# SI5324_CDR_WR_clocks.net
KiCad netlist of a schematic drawn in Altium Designer
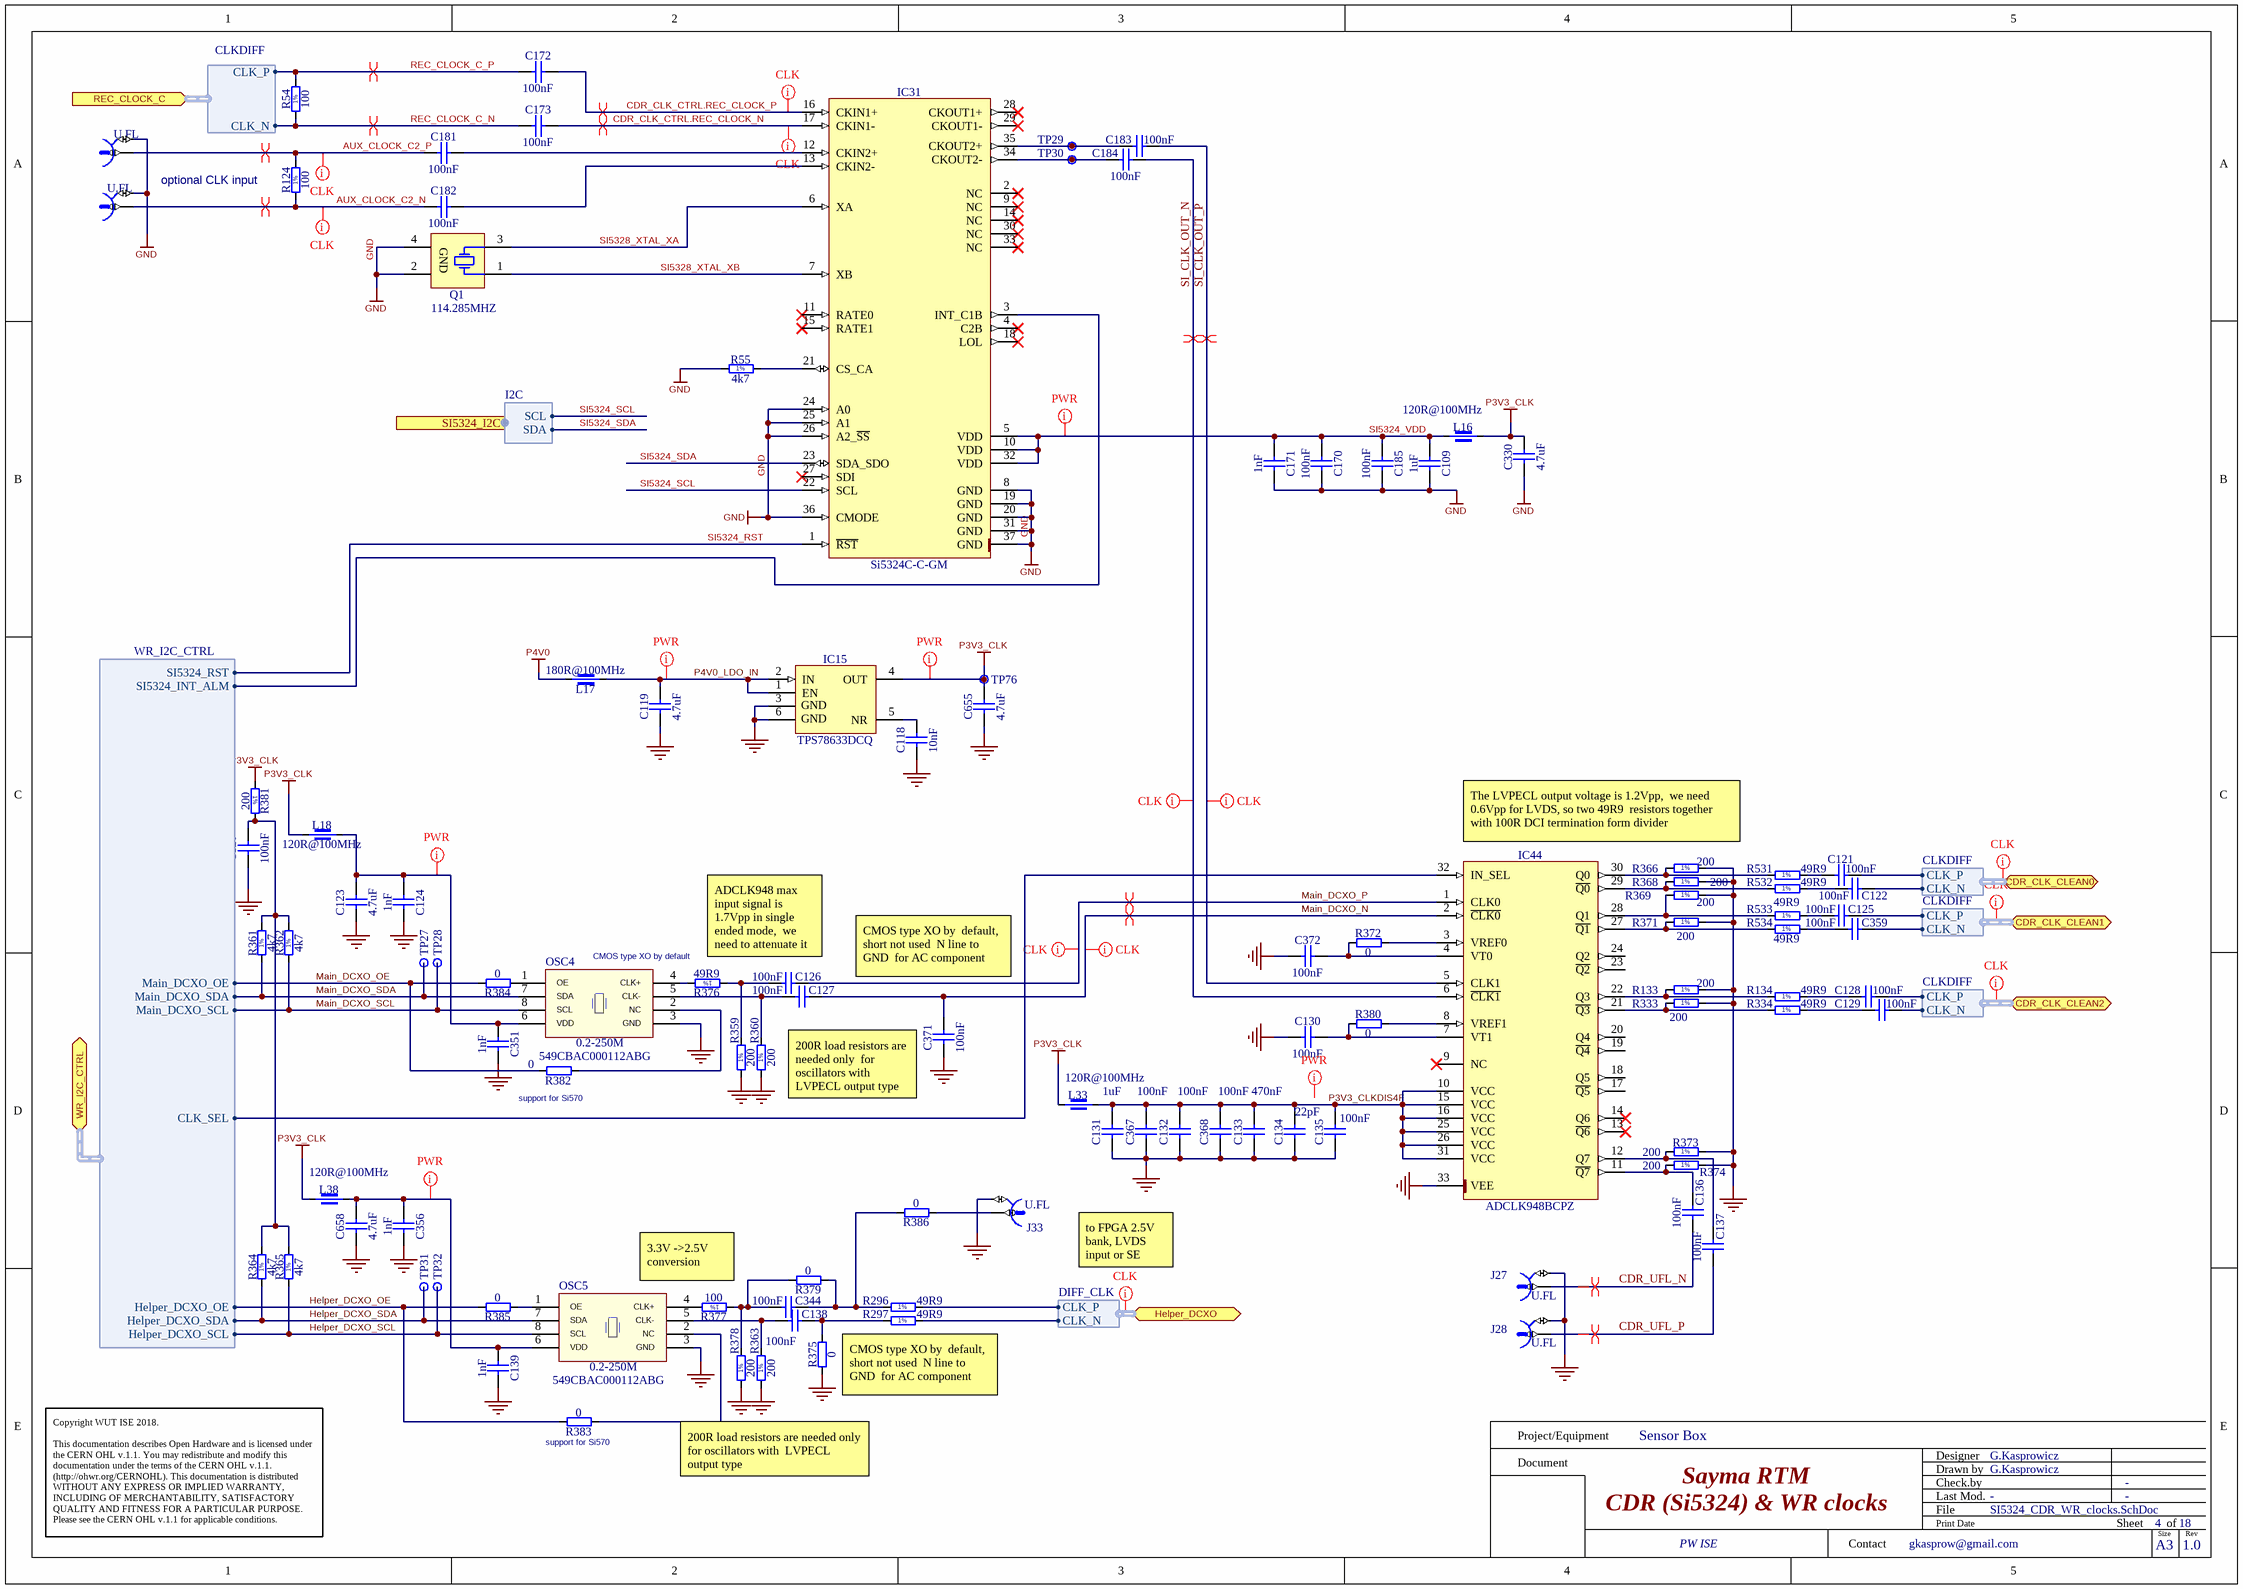
[diagram p0: SI5324_CDR_WR_clocks.SchDoc]

(export (version "E")
  (design (tool "Eeschema 10.0.6"))
  (components
    (comp (ref "C109")
      (value "1uF")
      (footprint "CAPC1005X55N")
      (description "Non-polarised capacitor")
      (fields
        (field (name "MANUFACTURER PART NUMBER") "CC0402_1UF_16V_10%_X5R")
        (field (name "MANUFACTURER") "GENERIC")
        (field (name "AUTHOR") "CERN DEM JLC")
      )
      (libsource (lib "Capacitors") (part "Capacitor - non polarized"))
    )
    (comp (ref "C118")
      (value "10nF")
      (footprint "CAPC1608X87N")
      (description "Non-polarised capacitor")
      (fields
        (field (name "PART NUMBER") "CC0603_10NF_50V_5%_C0G")
        (field (name "VOLTAGE") "50V")
        (field (name "AUTHOR") "CERN DEM JLC")
      )
      (libsource (lib "Capacitors") (part "Capacitor - non polarized"))
    )
    (comp (ref "C119")
      (value "4.7uF")
      (footprint "CAPC1608X90N")
      (description "Non-polarised capacitor")
      (fields
        (field (name "MANUFACTURER PART NUMBER") "CC0603_4.7UF_25V_10%_X5R")
        (field (name "MANUFACTURER") "GENERIC")
        (field (name "AUTHOR") "CERN DEM JLC")
      )
      (libsource (lib "Capacitors") (part "Capacitor - non polarized"))
    )
    (comp (ref "C120")
      (value "100nF")
      (footprint "CAPC0603X33N")
      (description "Non-polarised capacitor")
      (fields
        (field (name "MANUFACTURER PART NUMBER") "CC0201_100NF_6.3V_10%_X5R")
        (field (name "MANUFACTURER") "GENERIC")
        (field (name "AUTHOR") "CERN DEM JLC")
      )
      (libsource (lib "Capacitors") (part "Capacitor - non polarized"))
    )
    (comp (ref "C121")
      (value "100nF")
      (footprint "CAPC0603X33N")
      (description "Non-polarised capacitor")
      (fields
        (field (name "MANUFACTURER PART NUMBER") "CC0201_100NF_6.3V_10%_X5R")
        (field (name "MANUFACTURER") "GENERIC")
        (field (name "AUTHOR") "CERN DEM JLC")
      )
      (libsource (lib "Capacitors") (part "Capacitor - non polarized"))
    )
    (comp (ref "C122")
      (value "100nF")
      (footprint "CAPC0603X33N")
      (description "Non-polarised capacitor")
      (fields
        (field (name "MANUFACTURER PART NUMBER") "CC0201_100NF_6.3V_10%_X5R")
        (field (name "MANUFACTURER") "GENERIC")
        (field (name "AUTHOR") "CERN DEM JLC")
      )
      (libsource (lib "Capacitors") (part "Capacitor - non polarized"))
    )
    (comp (ref "C123")
      (value "4.7uF")
      (footprint "CAPC1608X90N")
      (description "Non-polarised capacitor")
      (fields
        (field (name "MANUFACTURER PART NUMBER") "CC0603_4.7UF_25V_10%_X5R")
        (field (name "MANUFACTURER") "GENERIC")
        (field (name "AUTHOR") "CERN DEM JLC")
      )
      (libsource (lib "Capacitors") (part "Capacitor - non polarized"))
    )
    (comp (ref "C124")
      (value "1nF")
      (footprint "CAPC0603X33N")
      (description "Non-polarised capacitor")
      (fields
        (field (name "MANUFACTURER PART NUMBER") "CC0201_1NF_16V_10%_X5R")
        (field (name "MANUFACTURER") "GENERIC")
        (field (name "AUTHOR") "CERN DEM JLC")
      )
      (libsource (lib "Capacitors") (part "Capacitor - non polarized"))
    )
    (comp (ref "C125")
      (value "100nF")
      (footprint "CAPC0603X33N")
      (description "Non-polarised capacitor")
      (fields
        (field (name "MANUFACTURER PART NUMBER") "CC0201_100NF_6.3V_10%_X5R")
        (field (name "MANUFACTURER") "GENERIC")
        (field (name "AUTHOR") "CERN DEM JLC")
      )
      (libsource (lib "Capacitors") (part "Capacitor - non polarized"))
    )
    (comp (ref "C126")
      (value "100nF")
      (footprint "CAPC1005X55N")
      (description "Non-polarised capacitor")
      (fields
        (field (name "MANUFACTURER PART NUMBER") "CC0402_100NF_16V_10%_X5R")
        (field (name "MANUFACTURER") "GENERIC")
        (field (name "AUTHOR") "CERN DEM JLC")
      )
      (libsource (lib "Capacitors") (part "Capacitor - non polarized"))
    )
    (comp (ref "C127")
      (value "100nF")
      (footprint "CAPC1005X55N")
      (description "Non-polarised capacitor")
      (fields
        (field (name "MANUFACTURER PART NUMBER") "CC0402_100NF_16V_10%_X5R")
        (field (name "MANUFACTURER") "GENERIC")
        (field (name "AUTHOR") "CERN DEM JLC")
      )
      (libsource (lib "Capacitors") (part "Capacitor - non polarized"))
    )
    (comp (ref "C128")
      (value "100nF")
      (footprint "CAPC0603X33N")
      (description "Non-polarised capacitor")
      (fields
        (field (name "MANUFACTURER PART NUMBER") "CC0201_100NF_6.3V_10%_X5R")
        (field (name "MANUFACTURER") "GENERIC")
        (field (name "AUTHOR") "CERN DEM JLC")
      )
      (libsource (lib "Capacitors") (part "Capacitor - non polarized"))
    )
    (comp (ref "C129")
      (value "100nF")
      (footprint "CAPC0603X33N")
      (description "Non-polarised capacitor")
      (fields
        (field (name "MANUFACTURER PART NUMBER") "CC0201_100NF_6.3V_10%_X5R")
        (field (name "MANUFACTURER") "GENERIC")
        (field (name "AUTHOR") "CERN DEM JLC")
      )
      (libsource (lib "Capacitors") (part "Capacitor - non polarized"))
    )
    (comp (ref "C130")
      (value "100nF")
      (footprint "CAPC0603X33N")
      (description "Non-polarised capacitor")
      (fields
        (field (name "MANUFACTURER PART NUMBER") "CC0201_100NF_6.3V_10%_X5R")
        (field (name "MANUFACTURER") "GENERIC")
        (field (name "AUTHOR") "CERN DEM JLC")
      )
      (libsource (lib "Capacitors") (part "Capacitor - non polarized"))
    )
    (comp (ref "C131")
      (value "1uF")
      (footprint "CAPC1005X55N")
      (description "Non-polarised capacitor")
      (fields
        (field (name "MANUFACTURER PART NUMBER") "CC0402_1UF_16V_10%_X5R")
        (field (name "MANUFACTURER") "GENERIC")
        (field (name "AUTHOR") "CERN DEM JLC")
      )
      (libsource (lib "Capacitors") (part "Capacitor - non polarized"))
    )
    (comp (ref "C132")
      (value "100nF")
      (footprint "CAPC0603X33N")
      (description "Non-polarised capacitor")
      (fields
        (field (name "MANUFACTURER PART NUMBER") "CC0201_100NF_6.3V_10%_X5R")
        (field (name "MANUFACTURER") "GENERIC")
        (field (name "AUTHOR") "CERN DEM JLC")
      )
      (libsource (lib "Capacitors") (part "Capacitor - non polarized"))
    )
    (comp (ref "C133")
      (value "470nF")
      (footprint "CAPC1005X55N")
      (description "Non-polarised capacitor")
      (fields
        (field (name "MANUFACTURER PART NUMBER") "CC0402_470NF_16V_10%_X5R")
        (field (name "MANUFACTURER") "GENERIC")
        (field (name "AUTHOR") "CERN DEM JLC")
      )
      (libsource (lib "Capacitors") (part "Capacitor - non polarized"))
    )
    (comp (ref "C134")
      (value "22pF")
      (footprint "CAPC1005X55N")
      (description "Non-polarised capacitor")
      (fields
        (field (name "MANUFACTURER PART NUMBER") "CC0402_22PF_50V_5%_C0G")
        (field (name "MANUFACTURER") "GENERIC")
        (field (name "AUTHOR") "CERN DEM JLC")
      )
      (libsource (lib "Capacitors") (part "Capacitor - non polarized"))
    )
    (comp (ref "C135")
      (value "100nF")
      (footprint "CAPC0603X33N")
      (description "Non-polarised capacitor")
      (fields
        (field (name "MANUFACTURER PART NUMBER") "CC0201_100NF_6.3V_10%_X5R")
        (field (name "MANUFACTURER") "GENERIC")
        (field (name "AUTHOR") "CERN DEM JLC")
      )
      (libsource (lib "Capacitors") (part "Capacitor - non polarized"))
    )
    (comp (ref "C136")
      (value "100nF")
      (footprint "CAPC0603X33N")
      (description "Non-polarised capacitor")
      (fields
        (field (name "MANUFACTURER PART NUMBER") "CC0201_100NF_6.3V_10%_X5R")
        (field (name "MANUFACTURER") "GENERIC")
        (field (name "AUTHOR") "CERN DEM JLC")
      )
      (libsource (lib "Capacitors") (part "Capacitor - non polarized"))
    )
    (comp (ref "C137")
      (value "100nF")
      (footprint "CAPC0603X33N")
      (description "Non-polarised capacitor")
      (fields
        (field (name "MANUFACTURER PART NUMBER") "CC0201_100NF_6.3V_10%_X5R")
        (field (name "MANUFACTURER") "GENERIC")
        (field (name "AUTHOR") "CERN DEM JLC")
      )
      (libsource (lib "Capacitors") (part "Capacitor - non polarized"))
    )
    (comp (ref "C138")
      (value "100nF")
      (footprint "CAPC1005X55N")
      (description "Non-polarised capacitor")
      (fields
        (field (name "MANUFACTURER PART NUMBER") "CC0402_100NF_16V_10%_X5R")
        (field (name "MANUFACTURER") "GENERIC")
        (field (name "AUTHOR") "CERN DEM JLC")
      )
      (libsource (lib "Capacitors") (part "Capacitor - non polarized"))
    )
    (comp (ref "C139")
      (value "1nF")
      (footprint "CAPC0603X33N")
      (description "Non-polarised capacitor")
      (fields
        (field (name "MANUFACTURER PART NUMBER") "CC0201_1NF_16V_10%_X5R")
        (field (name "MANUFACTURER") "GENERIC")
        (field (name "AUTHOR") "CERN DEM JLC")
      )
      (libsource (lib "Capacitors") (part "Capacitor - non polarized"))
    )
    (comp (ref "C170")
      (value "100nF")
      (footprint "CAPC0603X33N")
      (description "Non-polarised capacitor")
      (fields
        (field (name "MANUFACTURER PART NUMBER") "CC0201_100NF_6.3V_10%_X5R")
        (field (name "MANUFACTURER") "GENERIC")
        (field (name "AUTHOR") "CERN DEM JLC")
      )
      (libsource (lib "Capacitors") (part "Capacitor - non polarized"))
    )
    (comp (ref "C171")
      (value "1nF")
      (footprint "CAPC0603X33N")
      (description "Non-polarised capacitor")
      (fields
        (field (name "MANUFACTURER PART NUMBER") "CC0201_1NF_16V_10%_X5R")
        (field (name "MANUFACTURER") "GENERIC")
        (field (name "AUTHOR") "CERN DEM JLC")
      )
      (libsource (lib "Capacitors") (part "Capacitor - non polarized"))
    )
    (comp (ref "C172")
      (value "100nF")
      (footprint "CAPC0603X33N")
      (description "Non-polarised capacitor")
      (fields
        (field (name "MANUFACTURER PART NUMBER") "CC0201_100NF_6.3V_10%_X5R")
        (field (name "MANUFACTURER") "GENERIC")
        (field (name "AUTHOR") "CERN DEM JLC")
      )
      (libsource (lib "Capacitors") (part "Capacitor - non polarized"))
    )
    (comp (ref "C173")
      (value "100nF")
      (footprint "CAPC0603X33N")
      (description "Non-polarised capacitor")
      (fields
        (field (name "MANUFACTURER PART NUMBER") "CC0201_100NF_6.3V_10%_X5R")
        (field (name "MANUFACTURER") "GENERIC")
        (field (name "AUTHOR") "CERN DEM JLC")
      )
      (libsource (lib "Capacitors") (part "Capacitor - non polarized"))
    )
    (comp (ref "C181")
      (value "100nF")
      (footprint "CAPC0603X33N")
      (description "Non-polarised capacitor")
      (fields
        (field (name "MANUFACTURER PART NUMBER") "CC0201_100NF_6.3V_10%_X5R")
        (field (name "MANUFACTURER") "GENERIC")
        (field (name "AUTHOR") "CERN DEM JLC")
      )
      (libsource (lib "Capacitors") (part "Capacitor - non polarized"))
    )
    (comp (ref "C182")
      (value "100nF")
      (footprint "CAPC0603X33N")
      (description "Non-polarised capacitor")
      (fields
        (field (name "MANUFACTURER PART NUMBER") "CC0201_100NF_6.3V_10%_X5R")
        (field (name "MANUFACTURER") "GENERIC")
        (field (name "AUTHOR") "CERN DEM JLC")
      )
      (libsource (lib "Capacitors") (part "Capacitor - non polarized"))
    )
    (comp (ref "C183")
      (value "100nF")
      (footprint "CAPC0603X33N")
      (description "Non-polarised capacitor")
      (fields
        (field (name "MANUFACTURER PART NUMBER") "CC0201_100NF_6.3V_10%_X5R")
        (field (name "MANUFACTURER") "GENERIC")
        (field (name "AUTHOR") "CERN DEM JLC")
      )
      (libsource (lib "Capacitors") (part "Capacitor - non polarized"))
    )
    (comp (ref "C184")
      (value "100nF")
      (footprint "CAPC0603X33N")
      (description "Non-polarised capacitor")
      (fields
        (field (name "MANUFACTURER PART NUMBER") "CC0201_100NF_6.3V_10%_X5R")
        (field (name "MANUFACTURER") "GENERIC")
        (field (name "AUTHOR") "CERN DEM JLC")
      )
      (libsource (lib "Capacitors") (part "Capacitor - non polarized"))
    )
    (comp (ref "C185")
      (value "100nF")
      (footprint "CAPC0603X33N")
      (description "Non-polarised capacitor")
      (fields
        (field (name "MANUFACTURER PART NUMBER") "CC0201_100NF_6.3V_10%_X5R")
        (field (name "MANUFACTURER") "GENERIC")
        (field (name "AUTHOR") "CERN DEM JLC")
      )
      (libsource (lib "Capacitors") (part "Capacitor - non polarized"))
    )
    (comp (ref "C330")
      (value "4.7uF")
      (footprint "CAPC1608X90N")
      (description "Non-polarised capacitor")
      (fields
        (field (name "MANUFACTURER PART NUMBER") "CC0603_4.7UF_25V_10%_X5R")
        (field (name "MANUFACTURER") "GENERIC")
        (field (name "AUTHOR") "CERN DEM JLC")
      )
      (libsource (lib "Capacitors") (part "Capacitor - non polarized"))
    )
    (comp (ref "C344")
      (value "100nF")
      (footprint "CAPC1005X55N")
      (description "Non-polarised capacitor")
      (fields
        (field (name "MANUFACTURER PART NUMBER") "CC0402_100NF_16V_10%_X5R")
        (field (name "MANUFACTURER") "GENERIC")
        (field (name "AUTHOR") "CERN DEM JLC")
      )
      (libsource (lib "Capacitors") (part "Capacitor - non polarized"))
    )
    (comp (ref "C351")
      (value "1nF")
      (footprint "CAPC0603X33N")
      (description "Non-polarised capacitor")
      (fields
        (field (name "MANUFACTURER PART NUMBER") "CC0201_1NF_16V_10%_X5R")
        (field (name "MANUFACTURER") "GENERIC")
        (field (name "AUTHOR") "CERN DEM JLC")
      )
      (libsource (lib "Capacitors") (part "Capacitor - non polarized"))
    )
    (comp (ref "C356")
      (value "1nF")
      (footprint "CAPC0603X33N")
      (description "Non-polarised capacitor")
      (fields
        (field (name "MANUFACTURER PART NUMBER") "CC0201_1NF_16V_10%_X5R")
        (field (name "MANUFACTURER") "GENERIC")
        (field (name "AUTHOR") "CERN DEM JLC")
      )
      (libsource (lib "Capacitors") (part "Capacitor - non polarized"))
    )
    (comp (ref "C359")
      (value "100nF")
      (footprint "CAPC0603X33N")
      (description "Non-polarised capacitor")
      (fields
        (field (name "MANUFACTURER PART NUMBER") "CC0201_100NF_6.3V_10%_X5R")
        (field (name "MANUFACTURER") "GENERIC")
        (field (name "AUTHOR") "CERN DEM JLC")
      )
      (libsource (lib "Capacitors") (part "Capacitor - non polarized"))
    )
    (comp (ref "C367")
      (value "100nF")
      (footprint "CAPC0603X33N")
      (description "Non-polarised capacitor")
      (fields
        (field (name "MANUFACTURER PART NUMBER") "CC0201_100NF_6.3V_10%_X5R")
        (field (name "MANUFACTURER") "GENERIC")
        (field (name "AUTHOR") "CERN DEM JLC")
      )
      (libsource (lib "Capacitors") (part "Capacitor - non polarized"))
    )
    (comp (ref "C368")
      (value "100nF")
      (footprint "CAPC0603X33N")
      (description "Non-polarised capacitor")
      (fields
        (field (name "MANUFACTURER PART NUMBER") "CC0201_100NF_6.3V_10%_X5R")
        (field (name "MANUFACTURER") "GENERIC")
        (field (name "AUTHOR") "CERN DEM JLC")
      )
      (libsource (lib "Capacitors") (part "Capacitor - non polarized"))
    )
    (comp (ref "C371")
      (value "100nF")
      (footprint "CAPC0603X33N")
      (description "Non-polarised capacitor")
      (fields
        (field (name "MANUFACTURER PART NUMBER") "CC0201_100NF_6.3V_10%_X5R")
        (field (name "MANUFACTURER") "GENERIC")
        (field (name "AUTHOR") "CERN DEM JLC")
      )
      (libsource (lib "Capacitors") (part "Capacitor - non polarized"))
    )
    (comp (ref "C372")
      (value "100nF")
      (footprint "CAPC0603X33N")
      (description "Non-polarised capacitor")
      (fields
        (field (name "MANUFACTURER PART NUMBER") "CC0201_100NF_6.3V_10%_X5R")
        (field (name "MANUFACTURER") "GENERIC")
        (field (name "AUTHOR") "CERN DEM JLC")
      )
      (libsource (lib "Capacitors") (part "Capacitor - non polarized"))
    )
    (comp (ref "C655")
      (value "4.7uF")
      (footprint "CAPC1608X90N")
      (description "Non-polarised capacitor")
      (fields
        (field (name "MANUFACTURER PART NUMBER") "CC0603_4.7UF_25V_10%_X5R")
        (field (name "MANUFACTURER") "GENERIC")
        (field (name "AUTHOR") "CERN DEM JLC")
      )
      (libsource (lib "Capacitors") (part "Capacitor - non polarized"))
    )
    (comp (ref "C658")
      (value "4.7uF")
      (footprint "CAPC1608X90N")
      (description "Non-polarised capacitor")
      (fields
        (field (name "MANUFACTURER PART NUMBER") "CC0603_4.7UF_25V_10%_X5R")
        (field (name "MANUFACTURER") "GENERIC")
        (field (name "AUTHOR") "CERN DEM JLC")
      )
      (libsource (lib "Capacitors") (part "Capacitor - non polarized"))
    )
    (comp (ref "IC15")
      (value "TPS78633DCQ")
      (footprint "SOT127P700X180-6N")
      (description "Ultralow-Noise, High-PSRR, Fast, RF, 1.5A Low-Dropout Linear Regulator")
      (fields (field (name "MANUFACTURER") "TEXAS INSTRUMENTS") (field (name "AUTHOR") "CERN DEM JMW"))
      (libsource (lib "ICs And Semiconductors") (part "TPS786xxDCQ"))
    )
    (comp (ref "IC31")
      (value "Si5324C-C-GM")
      (footprint "QFN50P600X600X90-37N-S425")
      (description "Any Frequency Precision Clock Multiplier/Jitter Attenuator")
      (fields (field (name "MANUFACTURER") "SILICON LABS") (field (name "AUTHOR") "CERN DEM JLC"))
      (libsource (lib "ICs And Semiconductors") (part "Si5324"))
    )
    (comp (ref "IC44")
      (value "ADCLK948BCPZ")
      (footprint "QFN50P500X500X80-33N-S285")
      (description "Two Selectable Inputs, 8 LVPECL Outputs, SiGe Clock Fanout Buffer")
      (fields (field (name "MANUFACTURER") "ANALOG DEVICES") (field (name "AUTHOR") "CERN DEM MR"))
      (libsource (lib "ICs And Semiconductors") (part "ADCLK948"))
    )
    (comp (ref "J5")
      (value "U.FL")
      (footprint "HIROSE_U.FL-R-SMT-1(10)")
      (fields
        (field (name "FAMILY") "U.FL")
        (field (name "MANUFACTURER PART NUMBER") "U.FL-R-SMT-1(10)")
        (field (name "MANUFACTURER") "HIROSE (HRS)")
        (field (name "PART NUMBER") "HIROSE_U.FL-R-SMT-1(10)")
        (field (name "AUTHOR") "CERN DEM JLC")
      )
      (libsource (lib "Connectors") (part "Coax_1Male_1Shield"))
    )
    (comp (ref "J6")
      (value "U.FL")
      (footprint "HIROSE_U.FL-R-SMT-1(10)")
      (fields
        (field (name "FAMILY") "U.FL")
        (field (name "MANUFACTURER PART NUMBER") "U.FL-R-SMT-1(10)")
        (field (name "MANUFACTURER") "HIROSE (HRS)")
        (field (name "PART NUMBER") "HIROSE_U.FL-R-SMT-1(10)")
        (field (name "AUTHOR") "CERN DEM JLC")
      )
      (libsource (lib "Connectors") (part "Coax_1Male_1Shield"))
    )
    (comp (ref "J27")
      (value "U.FL")
      (footprint "HIROSE_U.FL-R-SMT-1(10)")
      (fields
        (field (name "MANUFACTURER PART NUMBER") "U.FL-R-SMT-1(10)")
        (field (name "MANUFACTURER") "HIROSE (HRS)")
        (field (name "PART NUMBER") "HIROSE_U.FL-R-SMT-1(10)")
        (field (name "AUTHOR") "CERN DEM JLC")
      )
      (libsource (lib "Connectors") (part "Coax_1Male_1Shield"))
    )
    (comp (ref "J28")
      (value "U.FL")
      (footprint "HIROSE_U.FL-R-SMT-1(10)")
      (fields
        (field (name "MANUFACTURER PART NUMBER") "U.FL-R-SMT-1(10)")
        (field (name "MANUFACTURER") "HIROSE (HRS)")
        (field (name "PART NUMBER") "HIROSE_U.FL-R-SMT-1(10)")
        (field (name "AUTHOR") "CERN DEM JLC")
      )
      (libsource (lib "Connectors") (part "Coax_1Male_1Shield"))
    )
    (comp (ref "J33")
      (value "U.FL")
      (footprint "HIROSE_U.FL-R-SMT-1(10)")
      (fields
        (field (name "MANUFACTURER PART NUMBER") "U.FL-R-SMT-1(10)")
        (field (name "MANUFACTURER") "HIROSE (HRS)")
        (field (name "PART NUMBER") "HIROSE_U.FL-R-SMT-1(10)")
        (field (name "AUTHOR") "CERN DEM JLC")
      )
      (libsource (lib "") (part "Coax_1Male_1Shield_1"))
    )
    (comp (ref "L16")
      (value "120R@100MHz")
      (footprint "INDC1608X95N")
      (fields
        (field (name "MANUFACTURER PART NUMBER") "BLM18PG121SN1D")
        (field (name "MANUFACTURER") "MURATA")
        (field (name "PART NUMBER") "IND0603_MURATA_BLM18PG121SN1D")
        (field (name "AUTHOR") "CERN DEM BC")
      )
      (libsource (lib "") (part "Ferrite Bead_1"))
    )
    (comp (ref "L17")
      (value "180R@100MHz")
      (footprint "INDC4516X180N")
      (fields
        (field (name "MANUFACTURER PART NUMBER") "BLM41PG181SN1L")
        (field (name "MANUFACTURER") "MURATA")
        (field (name "PART NUMBER") "IND1806_MURATA_BLM41PG181SN1L")
        (field (name "AUTHOR") "CERN DEM JLC")
      )
      (libsource (lib "") (part "Ferrite Bead_2"))
    )
    (comp (ref "L18")
      (value "120R@100MHz")
      (footprint "INDC1608X95N")
      (fields
        (field (name "MANUFACTURER PART NUMBER") "BLM18PG121SN1D")
        (field (name "MANUFACTURER") "MURATA")
        (field (name "PART NUMBER") "IND0603_MURATA_BLM18PG121SN1D")
        (field (name "AUTHOR") "CERN DEM BC")
      )
      (libsource (lib "Inductors & Transformers") (part "Ferrite Bead"))
    )
    (comp (ref "L33")
      (value "120R@100MHz")
      (footprint "INDC1608X95N")
      (fields
        (field (name "MANUFACTURER PART NUMBER") "BLM18PG121SN1D")
        (field (name "MANUFACTURER") "MURATA")
        (field (name "PART NUMBER") "IND0603_MURATA_BLM18PG121SN1D")
        (field (name "AUTHOR") "CERN DEM BC")
      )
      (libsource (lib "Inductors & Transformers") (part "Ferrite Bead"))
    )
    (comp (ref "L38")
      (value "120R@100MHz")
      (footprint "INDC1608X95N")
      (fields
        (field (name "MANUFACTURER PART NUMBER") "BLM18PG121SN1D")
        (field (name "MANUFACTURER") "MURATA")
        (field (name "PART NUMBER") "IND0603_MURATA_BLM18PG121SN1D")
        (field (name "AUTHOR") "CERN DEM BC")
      )
      (libsource (lib "Inductors & Transformers") (part "Ferrite Bead"))
    )
    (comp (ref "OSC4")
      (value "0.2-250M")
      (footprint "OSC_SILICON-LAB_SI549")
      (fields
        (field (name "MANUFACTURER PART NUMBER") "549CBAC000112ABG")
        (field (name "MANUFACTURER") "Silabs")
        (field (name "PART NUMBER") "OSC_0.2_250M_SILICON-LAB_549CBAC000112ABG")
      )
      (libsource (lib "LIBRARY_SCH") (part "OSC_SILICON-LAB_SI549"))
    )
    (comp (ref "OSC5")
      (value "0.2-250M")
      (footprint "OSC_SILICON-LAB_SI549")
      (fields
        (field (name "MANUFACTURER PART NUMBER") "549CBAC000112ABG")
        (field (name "MANUFACTURER") "Silabs")
        (field (name "PART NUMBER") "OSC_0.2_250M_SILICON-LAB_549CBAC000112ABG")
      )
      (libsource (lib "LIBRARY_SCH") (part "OSC_SILICON-LAB_SI549"))
    )
    (comp (ref "Q1")
      (value "114.285MHZ")
      (footprint "XTAL_CONNOR_CS")
      (description "Crystal 4 pins 1=XTAL Control 2=GND3=XTAL 4=GND")
      (fields
        (field (name "MANUFACTURER PART NUMBER") "CS-023-114.285M")
        (field (name "MANUFACTURER") "CONNOR-WINFIELD")
        (field (name "AUTHOR") "CERN DEM JLC")
      )
      (libsource (lib "ICs And Semiconductors") (part "Quartz Crystal 1X 2GND 3X 4GND"))
    )
    (comp (ref "R54")
      (value "100")
      (footprint "RESC1005X40N")
      (description "Resistor - 1%")
      (fields
        (field (name "MANUFACTURER PART NUMBER") "R0402_100R_1%_0.0625W_100PPM")
        (field (name "MANUFACTURER") "GENERIC")
        (field (name "AUTHOR") "CERN DEM JLC")
      )
      (libsource (lib "Resistors") (part "Resistor - 1%"))
    )
    (comp (ref "R55")
      (value "4k7")
      (footprint "RESC1005X40N")
      (description "Resistor - 1%")
      (fields
        (field (name "MANUFACTURER PART NUMBER") "R0402_4K7_1%_0.0625W_100PPM")
        (field (name "MANUFACTURER") "GENERIC")
        (field (name "AUTHOR") "CERN DEM JLC")
      )
      (libsource (lib "Resistors") (part "Resistor - 1%"))
    )
    (comp (ref "R124")
      (value "100")
      (footprint "RESC1005X40N")
      (description "Resistor - 1%")
      (fields
        (field (name "MANUFACTURER PART NUMBER") "R0402_100R_1%_0.0625W_100PPM")
        (field (name "MANUFACTURER") "GENERIC")
        (field (name "AUTHOR") "CERN DEM JLC")
      )
      (libsource (lib "Resistors") (part "Resistor - 1%"))
    )
    (comp (ref "R133")
      (value "200")
      (footprint "RESC1005X40N")
      (description "Resistor - 1%")
      (fields
        (field (name "MANUFACTURER PART NUMBER") "R0402_200R_1%_0.0625W_100PPM")
        (field (name "MANUFACTURER") "GENERIC")
        (field (name "AUTHOR") "CERN DEM JLC")
      )
      (libsource (lib "Resistors") (part "Resistor - 1%"))
    )
    (comp (ref "R134")
      (value "49R9")
      (footprint "RESC1005X40N")
      (description "Resistor - 1%")
      (fields
        (field (name "MANUFACTURER PART NUMBER") "R0402_49R9_1%_0.0625W_100PPM")
        (field (name "MANUFACTURER") "GENERIC")
        (field (name "AUTHOR") "CERN DEM JLC")
      )
      (libsource (lib "Resistors") (part "Resistor - 1%"))
    )
    (comp (ref "R296")
      (value "49R9")
      (footprint "RESC1005X40N")
      (description "Resistor - 1%")
      (fields
        (field (name "MANUFACTURER PART NUMBER") "R0402_49R9_1%_0.0625W_100PPM")
        (field (name "MANUFACTURER") "GENERIC")
        (field (name "AUTHOR") "CERN DEM JLC")
      )
      (libsource (lib "Resistors") (part "Resistor - 1%"))
    )
    (comp (ref "R297")
      (value "49R9")
      (footprint "RESC1005X40N")
      (description "Resistor - 1%")
      (fields
        (field (name "MANUFACTURER PART NUMBER") "R0402_49R9_1%_0.0625W_100PPM")
        (field (name "MANUFACTURER") "GENERIC")
        (field (name "AUTHOR") "CERN DEM JLC")
      )
      (libsource (lib "Resistors") (part "Resistor - 1%"))
    )
    (comp (ref "R333")
      (value "200")
      (footprint "RESC1005X40N")
      (description "Resistor - 1%")
      (fields
        (field (name "MANUFACTURER PART NUMBER") "R0402_200R_1%_0.0625W_100PPM")
        (field (name "MANUFACTURER") "GENERIC")
        (field (name "AUTHOR") "CERN DEM JLC")
      )
      (libsource (lib "Resistors") (part "Resistor - 1%"))
    )
    (comp (ref "R334")
      (value "49R9")
      (footprint "RESC1005X40N")
      (description "Resistor - 1%")
      (fields
        (field (name "MANUFACTURER PART NUMBER") "R0402_49R9_1%_0.0625W_100PPM")
        (field (name "MANUFACTURER") "GENERIC")
        (field (name "AUTHOR") "CERN DEM JLC")
      )
      (libsource (lib "Resistors") (part "Resistor - 1%"))
    )
    (comp (ref "R359")
      (value "200")
      (footprint "RESC1005X40N")
      (description "Resistor - 1%")
      (fields
        (field (name "MANUFACTURER PART NUMBER") "R0402_200R_1%_0.0625W_100PPM")
        (field (name "MANUFACTURER") "GENERIC")
        (field (name "AUTHOR") "CERN DEM JLC")
      )
      (libsource (lib "Resistors") (part "Resistor - 1%"))
    )
    (comp (ref "R360")
      (value "200")
      (footprint "RESC1005X40N")
      (description "Resistor - 1%")
      (fields
        (field (name "MANUFACTURER PART NUMBER") "R0402_200R_1%_0.0625W_100PPM")
        (field (name "MANUFACTURER") "GENERIC")
        (field (name "AUTHOR") "CERN DEM JLC")
      )
      (libsource (lib "Resistors") (part "Resistor - 1%"))
    )
    (comp (ref "R361")
      (value "4k7")
      (footprint "RESC1005X40N")
      (description "Resistor - 1%")
      (fields
        (field (name "MANUFACTURER PART NUMBER") "R0402_4K7_1%_0.0625W_100PPM")
        (field (name "MANUFACTURER") "GENERIC")
        (field (name "AUTHOR") "CERN DEM JLC")
      )
      (libsource (lib "Resistors") (part "Resistor - 1%"))
    )
    (comp (ref "R362")
      (value "4k7")
      (footprint "RESC1005X40N")
      (description "Resistor - 1%")
      (fields
        (field (name "MANUFACTURER PART NUMBER") "R0402_4K7_1%_0.0625W_100PPM")
        (field (name "MANUFACTURER") "GENERIC")
        (field (name "AUTHOR") "CERN DEM JLC")
      )
      (libsource (lib "Resistors") (part "Resistor - 1%"))
    )
    (comp (ref "R363")
      (value "200")
      (footprint "RESC1005X40N")
      (description "Resistor - 1%")
      (fields
        (field (name "MANUFACTURER PART NUMBER") "R0402_200R_1%_0.0625W_100PPM")
        (field (name "MANUFACTURER") "GENERIC")
        (field (name "AUTHOR") "CERN DEM JLC")
      )
      (libsource (lib "Resistors") (part "Resistor - 1%"))
    )
    (comp (ref "R364")
      (value "4k7")
      (footprint "RESC1005X40N")
      (description "Resistor - 1%")
      (fields
        (field (name "MANUFACTURER PART NUMBER") "R0402_4K7_1%_0.0625W_100PPM")
        (field (name "MANUFACTURER") "GENERIC")
        (field (name "AUTHOR") "CERN DEM JLC")
      )
      (libsource (lib "Resistors") (part "Resistor - 1%"))
    )
    (comp (ref "R365")
      (value "4k7")
      (footprint "RESC1005X40N")
      (description "Resistor - 1%")
      (fields
        (field (name "MANUFACTURER PART NUMBER") "R0402_4K7_1%_0.0625W_100PPM")
        (field (name "MANUFACTURER") "GENERIC")
        (field (name "AUTHOR") "CERN DEM JLC")
      )
      (libsource (lib "Resistors") (part "Resistor - 1%"))
    )
    (comp (ref "R366")
      (value "200")
      (footprint "RESC1005X40N")
      (description "Resistor - 1%")
      (fields
        (field (name "MANUFACTURER PART NUMBER") "R0402_200R_1%_0.0625W_100PPM")
        (field (name "MANUFACTURER") "GENERIC")
        (field (name "AUTHOR") "CERN DEM JLC")
      )
      (libsource (lib "Resistors") (part "Resistor - 1%"))
    )
    (comp (ref "R368")
      (value "200")
      (footprint "RESC1005X40N")
      (description "Resistor - 1%")
      (fields
        (field (name "MANUFACTURER PART NUMBER") "R0402_200R_1%_0.0625W_100PPM")
        (field (name "MANUFACTURER") "GENERIC")
        (field (name "AUTHOR") "CERN DEM JLC")
      )
      (libsource (lib "Resistors") (part "Resistor - 1%"))
    )
    (comp (ref "R369")
      (value "200")
      (footprint "RESC1005X40N")
      (description "Resistor - 1%")
      (fields
        (field (name "MANUFACTURER PART NUMBER") "R0402_200R_1%_0.0625W_100PPM")
        (field (name "MANUFACTURER") "GENERIC")
        (field (name "AUTHOR") "CERN DEM JLC")
      )
      (libsource (lib "Resistors") (part "Resistor - 1%"))
    )
    (comp (ref "R371")
      (value "200")
      (footprint "RESC1005X40N")
      (description "Resistor - 1%")
      (fields
        (field (name "MANUFACTURER PART NUMBER") "R0402_200R_1%_0.0625W_100PPM")
        (field (name "MANUFACTURER") "GENERIC")
        (field (name "AUTHOR") "CERN DEM JLC")
      )
      (libsource (lib "Resistors") (part "Resistor - 1%"))
    )
    (comp (ref "R372")
      (value "0")
      (footprint "RESC1005X40N")
      (description "Resistor")
      (fields
        (field (name "MANUFACTURER PART NUMBER") "R0402_0R_JUMPER")
        (field (name "MANUFACTURER") "GENERIC")
        (field (name "AUTHOR") "CERN DEM JLC")
      )
      (libsource (lib "Resistors") (part "Resistor"))
    )
    (comp (ref "R373")
      (value "200")
      (footprint "RESC1005X40N")
      (description "Resistor - 1%")
      (fields
        (field (name "MANUFACTURER PART NUMBER") "R0402_200R_1%_0.0625W_100PPM")
        (field (name "MANUFACTURER") "GENERIC")
        (field (name "AUTHOR") "CERN DEM JLC")
      )
      (libsource (lib "Resistors") (part "Resistor - 1%"))
    )
    (comp (ref "R374")
      (value "200")
      (footprint "RESC1005X40N")
      (description "Resistor - 1%")
      (fields
        (field (name "MANUFACTURER PART NUMBER") "R0402_200R_1%_0.0625W_100PPM")
        (field (name "MANUFACTURER") "GENERIC")
        (field (name "AUTHOR") "CERN DEM JLC")
      )
      (libsource (lib "Resistors") (part "Resistor - 1%"))
    )
    (comp (ref "R375")
      (value "0")
      (footprint "RESC1005X40N")
      (description "Resistor")
      (fields
        (field (name "MANUFACTURER PART NUMBER") "R0402_0R_JUMPER")
        (field (name "MANUFACTURER") "GENERIC")
        (field (name "AUTHOR") "CERN DEM JLC")
      )
      (libsource (lib "Resistors") (part "Resistor"))
    )
    (comp (ref "R376")
      (value "49R9")
      (footprint "RESC1005X40N")
      (description "Resistor - 1%")
      (fields
        (field (name "MANUFACTURER PART NUMBER") "R0402_49R9_1%_0.0625W_100PPM")
        (field (name "MANUFACTURER") "GENERIC")
        (field (name "AUTHOR") "CERN DEM JLC")
      )
      (libsource (lib "Resistors") (part "Resistor - 1%"))
    )
    (comp (ref "R377")
      (value "100")
      (footprint "RESC1005X40N")
      (description "Resistor - 1%")
      (fields
        (field (name "MANUFACTURER PART NUMBER") "R0402_100R_1%_0.0625W_100PPM")
        (field (name "MANUFACTURER") "GENERIC")
        (field (name "AUTHOR") "CERN DEM JLC")
      )
      (libsource (lib "Resistors") (part "Resistor - 1%"))
    )
    (comp (ref "R378")
      (value "200")
      (footprint "RESC1005X40N")
      (description "Resistor - 1%")
      (fields
        (field (name "MANUFACTURER PART NUMBER") "R0402_200R_1%_0.0625W_100PPM")
        (field (name "MANUFACTURER") "GENERIC")
        (field (name "AUTHOR") "CERN DEM JLC")
      )
      (libsource (lib "Resistors") (part "Resistor - 1%"))
    )
    (comp (ref "R379")
      (value "0")
      (footprint "RESC1005X40N")
      (description "Resistor")
      (fields
        (field (name "MANUFACTURER PART NUMBER") "R0402_0R_JUMPER")
        (field (name "MANUFACTURER") "GENERIC")
        (field (name "AUTHOR") "CERN DEM JLC")
      )
      (libsource (lib "Resistors") (part "Resistor"))
    )
    (comp (ref "R380")
      (value "0")
      (footprint "RESC1005X40N")
      (description "Resistor")
      (fields
        (field (name "MANUFACTURER PART NUMBER") "R0402_0R_JUMPER")
        (field (name "MANUFACTURER") "GENERIC")
        (field (name "AUTHOR") "CERN DEM JLC")
      )
      (libsource (lib "Resistors") (part "Resistor"))
    )
    (comp (ref "R381")
      (value "200")
      (footprint "RESC1005X40N")
      (description "Resistor - 1%")
      (fields
        (field (name "MANUFACTURER PART NUMBER") "R0402_200R_1%_0.0625W_100PPM")
        (field (name "MANUFACTURER") "GENERIC")
        (field (name "AUTHOR") "CERN DEM JLC")
      )
      (libsource (lib "Resistors") (part "Resistor - 1%"))
    )
    (comp (ref "R382")
      (value "0")
      (footprint "RESC1005X40N")
      (description "Resistor")
      (fields
        (field (name "MANUFACTURER PART NUMBER") "R0402_0R_JUMPER")
        (field (name "MANUFACTURER") "GENERIC")
        (field (name "AUTHOR") "CERN DEM JLC")
      )
      (libsource (lib "Resistors") (part "Resistor"))
    )
    (comp (ref "R383")
      (value "0")
      (footprint "RESC1005X40N")
      (description "Resistor")
      (fields
        (field (name "MANUFACTURER PART NUMBER") "R0402_0R_JUMPER")
        (field (name "MANUFACTURER") "GENERIC")
        (field (name "AUTHOR") "CERN DEM JLC")
      )
      (libsource (lib "Resistors") (part "Resistor"))
    )
    (comp (ref "R384")
      (value "0")
      (footprint "RESC1005X40N")
      (description "Resistor")
      (fields
        (field (name "MANUFACTURER PART NUMBER") "R0402_0R_JUMPER")
        (field (name "MANUFACTURER") "GENERIC")
        (field (name "AUTHOR") "CERN DEM JLC")
      )
      (libsource (lib "Resistors") (part "Resistor"))
    )
    (comp (ref "R385")
      (value "0")
      (footprint "RESC1005X40N")
      (description "Resistor")
      (fields
        (field (name "MANUFACTURER PART NUMBER") "R0402_0R_JUMPER")
        (field (name "MANUFACTURER") "GENERIC")
        (field (name "AUTHOR") "CERN DEM JLC")
      )
      (libsource (lib "Resistors") (part "Resistor"))
    )
    (comp (ref "R386")
      (value "0")
      (footprint "RESC1005X40N")
      (description "Resistor")
      (fields
        (field (name "MANUFACTURER PART NUMBER") "R0402_0R_JUMPER")
        (field (name "MANUFACTURER") "GENERIC")
        (field (name "AUTHOR") "CERN DEM JLC")
      )
      (libsource (lib "Resistors") (part "Resistor"))
    )
    (comp (ref "R531")
      (value "49R9")
      (footprint "RESC1005X40N")
      (description "Resistor - 1%")
      (fields
        (field (name "MANUFACTURER PART NUMBER") "R0402_49R9_1%_0.0625W_100PPM")
        (field (name "MANUFACTURER") "GENERIC")
        (field (name "AUTHOR") "CERN DEM JLC")
      )
      (libsource (lib "Resistors") (part "Resistor - 1%"))
    )
    (comp (ref "R532")
      (value "49R9")
      (footprint "RESC1005X40N")
      (description "Resistor - 1%")
      (fields
        (field (name "MANUFACTURER PART NUMBER") "R0402_49R9_1%_0.0625W_100PPM")
        (field (name "MANUFACTURER") "GENERIC")
        (field (name "AUTHOR") "CERN DEM JLC")
      )
      (libsource (lib "Resistors") (part "Resistor - 1%"))
    )
    (comp (ref "R533")
      (value "49R9")
      (footprint "RESC1005X40N")
      (description "Resistor - 1%")
      (fields
        (field (name "MANUFACTURER PART NUMBER") "R0402_49R9_1%_0.0625W_100PPM")
        (field (name "MANUFACTURER") "GENERIC")
        (field (name "AUTHOR") "CERN DEM JLC")
      )
      (libsource (lib "Resistors") (part "Resistor - 1%"))
    )
    (comp (ref "R534")
      (value "49R9")
      (footprint "RESC1005X40N")
      (description "Resistor - 1%")
      (fields
        (field (name "MANUFACTURER PART NUMBER") "R0402_49R9_1%_0.0625W_100PPM")
        (field (name "MANUFACTURER") "GENERIC")
        (field (name "AUTHOR") "CERN DEM JLC")
      )
      (libsource (lib "Resistors") (part "Resistor - 1%"))
    )
    (comp (ref "TP27")
      (value "Test Point")
      (footprint "TPS127")
      (fields (field (name "PART NUMBER") "SMD_PAD_1.27X1.27MM") (field (name "AUTHOR") "CERN DEM JLC"))
      (libsource (lib "Eletro-mechanical") (part "Test Point"))
    )
    (comp (ref "TP28")
      (value "Test Point")
      (footprint "TPS127")
      (fields (field (name "PART NUMBER") "SMD_PAD_1.27X1.27MM") (field (name "AUTHOR") "CERN DEM JLC"))
      (libsource (lib "Eletro-mechanical") (part "Test Point"))
    )
    (comp (ref "TP29")
      (value "Test Point")
      (footprint "TPS127")
      (fields (field (name "PART NUMBER") "SMD_PAD_1.27X1.27MM") (field (name "AUTHOR") "CERN DEM JLC"))
      (libsource (lib "Eletro-mechanical") (part "Test Point"))
    )
    (comp (ref "TP30")
      (value "Test Point")
      (footprint "TPS127")
      (fields (field (name "PART NUMBER") "SMD_PAD_1.27X1.27MM") (field (name "AUTHOR") "CERN DEM JLC"))
      (libsource (lib "Eletro-mechanical") (part "Test Point"))
    )
    (comp (ref "TP31")
      (value "Test Point")
      (footprint "TPS127")
      (fields (field (name "PART NUMBER") "SMD_PAD_1.27X1.27MM") (field (name "AUTHOR") "CERN DEM JLC"))
      (libsource (lib "Eletro-mechanical") (part "Test Point"))
    )
    (comp (ref "TP32")
      (value "Test Point")
      (footprint "TPS127")
      (fields (field (name "PART NUMBER") "SMD_PAD_1.27X1.27MM") (field (name "AUTHOR") "CERN DEM JLC"))
      (libsource (lib "Eletro-mechanical") (part "Test Point"))
    )
    (comp (ref "TP76")
      (value "Test Point")
      (footprint "TPS127")
      (fields (field (name "PART NUMBER") "SMD_PAD_1.27X1.27MM") (field (name "AUTHOR") "CERN DEM JLC"))
      (libsource (lib "Eletro-mechanical") (part "Test Point"))
    )
  )
  (nets
    (net (code "5") (name "/AUX_CLOCK_C2_N") (class "Default")
      (node (ref "C182") (pin "2") (pinfunction "2_2") (pintype "passive"))
      (node (ref "J6") (pin "1") (pinfunction "1_1") (pintype "bidirectional"))
      (node (ref "R124") (pin "1") (pinfunction "1_1") (pintype "passive"))
    )
    (net (code "6") (name "/AUX_CLOCK_C2_P") (class "Default")
      (node (ref "C181") (pin "2") (pinfunction "2_2") (pintype "passive"))
      (node (ref "J5") (pin "1") (pinfunction "1_1") (pintype "bidirectional"))
      (node (ref "R124") (pin "2") (pinfunction "2_2") (pintype "passive"))
    )
    (net (code "7") (name "/CDR_CLK_CTRL.REC_CLOCK_N") (class "Default")
      (node (ref "C173") (pin "1") (pinfunction "1_1") (pintype "passive"))
      (node (ref "IC31") (pin "17") (pinfunction "CKIN1-_17") (pintype "input"))
    )
    (net (code "8") (name "/CDR_CLK_CTRL.REC_CLOCK_P") (class "Default")
      (node (ref "C172") (pin "1") (pinfunction "1_1") (pintype "passive"))
      (node (ref "IC31") (pin "16") (pinfunction "CKIN1+_16") (pintype "input"))
    )
    (net (code "9") (name "/CDR_UFL_N") (class "Default")
      (node (ref "C136") (pin "2") (pinfunction "2_2") (pintype "passive"))
      (node (ref "J27") (pin "1") (pinfunction "1_1") (pintype "bidirectional"))
    )
    (net (code "10") (name "/CDR_UFL_P") (class "Default")
      (node (ref "C137") (pin "2") (pinfunction "2_2") (pintype "passive"))
      (node (ref "J28") (pin "1") (pinfunction "1_1") (pintype "bidirectional"))
    )
    (net (code "11") (name "/CLK_SEL") (class "Default")
      (node (ref "IC44") (pin "32") (pinfunction "IN_SEL_32") (pintype "input"))
    )
    (net (code "12") (name "/Helper_DCXO_OE") (class "Default")
      (node (ref "R383") (pin "2") (pinfunction "2_2") (pintype "passive"))
      (node (ref "R385") (pin "2") (pinfunction "2_2") (pintype "passive"))
    )
    (net (code "13") (name "/Helper_DCXO_SCL") (class "Default")
      (node (ref "OSC5") (pin "8") (pinfunction "SCL_8") (pintype "passive"))
      (node (ref "R365") (pin "1") (pinfunction "1_1") (pintype "passive"))
      (node (ref "TP32") (pin "1") (pinfunction "1_1") (pintype "bidirectional"))
    )
    (net (code "14") (name "/Helper_DCXO_SDA") (class "Default")
      (node (ref "OSC5") (pin "7") (pinfunction "SDA_7") (pintype "passive"))
      (node (ref "R364") (pin "1") (pinfunction "1_1") (pintype "passive"))
      (node (ref "TP31") (pin "1") (pinfunction "1_1") (pintype "bidirectional"))
    )
    (net (code "15") (name "/Main_DCXO_N") (class "Default")
      (node (ref "C127") (pin "2") (pinfunction "2_2") (pintype "passive"))
      (node (ref "C371") (pin "2") (pinfunction "2_2") (pintype "passive"))
      (node (ref "IC44") (pin "2") (pinfunction "~{CLK0}_2") (pintype "input"))
    )
    (net (code "16") (name "/Main_DCXO_OE") (class "Default")
      (node (ref "R382") (pin "2") (pinfunction "2_2") (pintype "passive"))
      (node (ref "R384") (pin "2") (pinfunction "2_2") (pintype "passive"))
    )
    (net (code "17") (name "/Main_DCXO_P") (class "Default")
      (node (ref "C126") (pin "2") (pinfunction "2_2") (pintype "passive"))
      (node (ref "IC44") (pin "1") (pinfunction "CLK0_1") (pintype "input"))
    )
    (net (code "18") (name "/Main_DCXO_SCL") (class "Default")
      (node (ref "OSC4") (pin "8") (pinfunction "SCL_8") (pintype "passive"))
      (node (ref "R362") (pin "1") (pinfunction "1_1") (pintype "passive"))
      (node (ref "TP28") (pin "1") (pinfunction "1_1") (pintype "bidirectional"))
    )
    (net (code "19") (name "/Main_DCXO_SDA") (class "Default")
      (node (ref "OSC4") (pin "7") (pinfunction "SDA_7") (pintype "passive"))
      (node (ref "R361") (pin "1") (pinfunction "1_1") (pintype "passive"))
      (node (ref "TP27") (pin "1") (pinfunction "1_1") (pintype "bidirectional"))
    )
    (net (code "20") (name "/P3V3_CLKDIS4F") (class "Default")
      (node (ref "C131") (pin "1") (pinfunction "1_1") (pintype "passive"))
      (node (ref "C132") (pin "2") (pinfunction "2_2") (pintype "passive"))
      (node (ref "C133") (pin "2") (pinfunction "2_2") (pintype "passive"))
      (node (ref "C134") (pin "2") (pinfunction "2_2") (pintype "passive"))
      (node (ref "C135") (pin "2") (pinfunction "2_2") (pintype "passive"))
      (node (ref "C367") (pin "2") (pinfunction "2_2") (pintype "passive"))
      (node (ref "C368") (pin "2") (pinfunction "2_2") (pintype "passive"))
      (node (ref "IC44") (pin "10") (pinfunction "VCC_10") (pintype "power_in"))
      (node (ref "IC44") (pin "15") (pinfunction "VCC_15") (pintype "power_in"))
      (node (ref "IC44") (pin "16") (pinfunction "VCC_16") (pintype "power_in"))
      (node (ref "IC44") (pin "25") (pinfunction "VCC_25") (pintype "power_in"))
      (node (ref "IC44") (pin "26") (pinfunction "VCC_26") (pintype "power_in"))
      (node (ref "IC44") (pin "31") (pinfunction "VCC_31") (pintype "power_in"))
      (node (ref "L33") (pin "2") (pinfunction "2_2") (pintype "passive"))
    )
    (net (code "21") (name "/P4V0_LDO_IN") (class "Default")
      (node (ref "C119") (pin "2") (pinfunction "2_2") (pintype "passive"))
      (node (ref "IC15") (pin "1") (pinfunction "EN_1") (pintype "power_in"))
      (node (ref "IC15") (pin "2") (pinfunction "IN_2") (pintype "input"))
      (node (ref "L17") (pin "2") (pinfunction "2_2") (pintype "passive"))
    )
    (net (code "22") (name "/REC_CLOCK_C_N") (class "Default")
      (node (ref "C173") (pin "2") (pinfunction "2_2") (pintype "passive"))
      (node (ref "R54") (pin "1") (pinfunction "1_1") (pintype "passive"))
    )
    (net (code "23") (name "/REC_CLOCK_C_P") (class "Default")
      (node (ref "C172") (pin "2") (pinfunction "2_2") (pintype "passive"))
      (node (ref "R54") (pin "2") (pinfunction "2_2") (pintype "passive"))
    )
    (net (code "24") (name "/SI5324_INT_ALM") (class "Default")
      (node (ref "IC31") (pin "3") (pinfunction "INT_C1B_3") (pintype "output"))
    )
    (net (code "25") (name "/SI5324_RST") (class "Default")
      (node (ref "IC31") (pin "1") (pinfunction "~{RST}_1") (pintype "input"))
    )
    (net (code "26") (name "/SI5324_SCL") (class "Default")
      (node (ref "IC31") (pin "22") (pinfunction "SCL_22") (pintype "input"))
    )
    (net (code "27") (name "/SI5324_SDA") (class "Default")
      (node (ref "IC31") (pin "23") (pinfunction "SDA_SDO_23") (pintype "bidirectional"))
    )
    (net (code "28") (name "/SI5324_VDD") (class "Default")
      (node (ref "C109") (pin "1") (pinfunction "1_1") (pintype "passive"))
      (node (ref "C170") (pin "2") (pinfunction "2_2") (pintype "passive"))
      (node (ref "C171") (pin "2") (pinfunction "2_2") (pintype "passive"))
      (node (ref "C185") (pin "2") (pinfunction "2_2") (pintype "passive"))
      (node (ref "IC31") (pin "10") (pinfunction "VDD_10") (pintype "power_in"))
      (node (ref "IC31") (pin "32") (pinfunction "VDD_32") (pintype "power_in"))
      (node (ref "IC31") (pin "5") (pinfunction "VDD_5") (pintype "power_in"))
      (node (ref "L16") (pin "2") (pinfunction "2_2") (pintype "passive"))
    )
    (net (code "29") (name "/SI5328_XTAL_XA") (class "Default")
      (node (ref "IC31") (pin "6") (pinfunction "XA_6") (pintype "input"))
      (node (ref "Q1") (pin "3") (pinfunction "X_3") (pintype "passive"))
    )
    (net (code "30") (name "/SI5328_XTAL_XB") (class "Default")
      (node (ref "IC31") (pin "7") (pinfunction "XB_7") (pintype "input"))
      (node (ref "Q1") (pin "1") (pinfunction "X_1") (pintype "passive"))
    )
    (net (code "31") (name "/SI_CLK_OUT_N") (class "Default")
      (node (ref "C184") (pin "1") (pinfunction "1_1") (pintype "passive"))
      (node (ref "IC44") (pin "6") (pinfunction "~{CLK1}_6") (pintype "input"))
    )
    (net (code "32") (name "/SI_CLK_OUT_P") (class "Default")
      (node (ref "C183") (pin "1") (pinfunction "1_1") (pintype "passive"))
      (node (ref "IC44") (pin "5") (pinfunction "CLK1_5") (pintype "input"))
    )
    (net (code "37") (name "GND") (class "Default")
      (node (ref "C109") (pin "2") (pinfunction "2_2") (pintype "passive"))
      (node (ref "C118") (pin "1") (pinfunction "1_1") (pintype "passive"))
      (node (ref "C119") (pin "1") (pinfunction "1_1") (pintype "passive"))
      (node (ref "C120") (pin "1") (pinfunction "1_1") (pintype "passive"))
      (node (ref "C123") (pin "1") (pinfunction "1_1") (pintype "passive"))
      (node (ref "C124") (pin "1") (pinfunction "1_1") (pintype "passive"))
      (node (ref "C130") (pin "1") (pinfunction "1_1") (pintype "passive"))
      (node (ref "C131") (pin "2") (pinfunction "2_2") (pintype "passive"))
      (node (ref "C132") (pin "1") (pinfunction "1_1") (pintype "passive"))
      (node (ref "C133") (pin "1") (pinfunction "1_1") (pintype "passive"))
      (node (ref "C134") (pin "1") (pinfunction "1_1") (pintype "passive"))
      (node (ref "C135") (pin "1") (pinfunction "1_1") (pintype "passive"))
      (node (ref "C139") (pin "1") (pinfunction "1_1") (pintype "passive"))
      (node (ref "C170") (pin "1") (pinfunction "1_1") (pintype "passive"))
      (node (ref "C171") (pin "1") (pinfunction "1_1") (pintype "passive"))
      (node (ref "C185") (pin "1") (pinfunction "1_1") (pintype "passive"))
      (node (ref "C330") (pin "1") (pinfunction "1_1") (pintype "passive"))
      (node (ref "C351") (pin "1") (pinfunction "1_1") (pintype "passive"))
      (node (ref "C356") (pin "1") (pinfunction "1_1") (pintype "passive"))
      (node (ref "C367") (pin "1") (pinfunction "1_1") (pintype "passive"))
      (node (ref "C368") (pin "1") (pinfunction "1_1") (pintype "passive"))
      (node (ref "C371") (pin "1") (pinfunction "1_1") (pintype "passive"))
      (node (ref "C372") (pin "1") (pinfunction "1_1") (pintype "passive"))
      (node (ref "C655") (pin "1") (pinfunction "1_1") (pintype "passive"))
      (node (ref "C658") (pin "1") (pinfunction "1_1") (pintype "passive"))
      (node (ref "IC15") (pin "3") (pinfunction "GND_3") (pintype "power_in"))
      (node (ref "IC15") (pin "6") (pinfunction "GND_6") (pintype "power_in"))
      (node (ref "IC31") (pin "19") (pinfunction "GND_19") (pintype "power_in"))
      (node (ref "IC31") (pin "20") (pinfunction "GND_20") (pintype "power_in"))
      (node (ref "IC31") (pin "24") (pinfunction "A0_24") (pintype "input"))
      (node (ref "IC31") (pin "25") (pinfunction "A1_25") (pintype "input"))
      (node (ref "IC31") (pin "26") (pinfunction "A2_~{SS}_26") (pintype "input"))
      (node (ref "IC31") (pin "31") (pinfunction "GND_31") (pintype "power_in"))
      (node (ref "IC31") (pin "36") (pinfunction "CMODE_36") (pintype "input"))
      (node (ref "IC31") (pin "37") (pinfunction "GND_37") (pintype "power_in"))
      (node (ref "IC31") (pin "8") (pinfunction "GND_8") (pintype "power_in"))
      (node (ref "IC44") (pin "33") (pinfunction "VEE_33") (pintype "power_in"))
      (node (ref "J27") (pin "2") (pinfunction "2_2") (pintype "bidirectional"))
      (node (ref "J28") (pin "2") (pinfunction "2_2") (pintype "bidirectional"))
      (node (ref "J33") (pin "2") (pinfunction "2_2") (pintype "bidirectional"))
      (node (ref "J5") (pin "2") (pinfunction "2_2") (pintype "bidirectional"))
      (node (ref "J6") (pin "2") (pinfunction "2_2") (pintype "bidirectional"))
      (node (ref "OSC4") (pin "3") (pinfunction "GND_3") (pintype "passive"))
      (node (ref "OSC5") (pin "3") (pinfunction "GND_3") (pintype "passive"))
      (node (ref "Q1") (pin "2") (pinfunction "GND_2") (pintype "power_in"))
      (node (ref "Q1") (pin "4") (pinfunction "GND_4") (pintype "power_in"))
      (node (ref "R133") (pin "2") (pinfunction "2_2") (pintype "passive"))
      (node (ref "R333") (pin "2") (pinfunction "2_2") (pintype "passive"))
      (node (ref "R359") (pin "1") (pinfunction "1_1") (pintype "passive"))
      (node (ref "R360") (pin "1") (pinfunction "1_1") (pintype "passive"))
      (node (ref "R363") (pin "1") (pinfunction "1_1") (pintype "passive"))
      (node (ref "R366") (pin "2") (pinfunction "2_2") (pintype "passive"))
      (node (ref "R368") (pin "2") (pinfunction "2_2") (pintype "passive"))
      (node (ref "R369") (pin "2") (pinfunction "2_2") (pintype "passive"))
      (node (ref "R371") (pin "2") (pinfunction "2_2") (pintype "passive"))
      (node (ref "R373") (pin "2") (pinfunction "2_2") (pintype "passive"))
      (node (ref "R374") (pin "2") (pinfunction "2_2") (pintype "passive"))
      (node (ref "R375") (pin "1") (pinfunction "1_1") (pintype "passive"))
      (node (ref "R378") (pin "1") (pinfunction "1_1") (pintype "passive"))
      (node (ref "R55") (pin "1") (pinfunction "1_1") (pintype "passive"))
    )
    (net (code "38") (name "Net-(C120-Pad2)") (class "Default")
      (node (ref "C120") (pin "2") (pinfunction "2_2") (pintype "passive"))
      (node (ref "R361") (pin "2") (pinfunction "2_2") (pintype "passive"))
      (node (ref "R362") (pin "2") (pinfunction "2_2") (pintype "passive"))
      (node (ref "R364") (pin "2") (pinfunction "2_2") (pintype "passive"))
      (node (ref "R365") (pin "2") (pinfunction "2_2") (pintype "passive"))
      (node (ref "R381") (pin "2") (pinfunction "2_2") (pintype "passive"))
    )
    (net (code "39") (name "Net-(C121-Pad1)") (class "Default")
      (node (ref "C121") (pin "1") (pinfunction "1_1") (pintype "passive"))
      (node (ref "R531") (pin "2") (pinfunction "2_2") (pintype "passive"))
    )
    (net (code "40") (name "Net-(C122-Pad1)") (class "Default")
      (node (ref "C122") (pin "1") (pinfunction "1_1") (pintype "passive"))
      (node (ref "R532") (pin "2") (pinfunction "2_2") (pintype "passive"))
    )
    (net (code "41") (name "Net-(C125-Pad1)") (class "Default")
      (node (ref "C125") (pin "1") (pinfunction "1_1") (pintype "passive"))
      (node (ref "R533") (pin "2") (pinfunction "2_2") (pintype "passive"))
    )
    (net (code "42") (name "Net-(C126-Pad1)") (class "Default")
      (node (ref "C126") (pin "1") (pinfunction "1_1") (pintype "passive"))
      (node (ref "R359") (pin "2") (pinfunction "2_2") (pintype "passive"))
      (node (ref "R376") (pin "1") (pinfunction "1_1") (pintype "passive"))
    )
    (net (code "43") (name "Net-(C128-Pad1)") (class "Default")
      (node (ref "C128") (pin "1") (pinfunction "1_1") (pintype "passive"))
      (node (ref "R134") (pin "2") (pinfunction "2_2") (pintype "passive"))
    )
    (net (code "44") (name "Net-(C129-Pad1)") (class "Default")
      (node (ref "C129") (pin "1") (pinfunction "1_1") (pintype "passive"))
      (node (ref "R334") (pin "2") (pinfunction "2_2") (pintype "passive"))
    )
    (net (code "45") (name "Net-(C138-Pad2)") (class "Default")
      (node (ref "C138") (pin "2") (pinfunction "2_2") (pintype "passive"))
      (node (ref "R297") (pin "1") (pinfunction "1_1") (pintype "passive"))
      (node (ref "R375") (pin "2") (pinfunction "2_2") (pintype "passive"))
    )
    (net (code "46") (name "Net-(C344-Pad1)") (class "Default")
      (node (ref "C344") (pin "1") (pinfunction "1_1") (pintype "passive"))
      (node (ref "R377") (pin "1") (pinfunction "1_1") (pintype "passive"))
      (node (ref "R378") (pin "2") (pinfunction "2_2") (pintype "passive"))
      (node (ref "R379") (pin "2") (pinfunction "2_2") (pintype "passive"))
    )
    (net (code "47") (name "Net-(C344-Pad2)") (class "Default")
      (node (ref "C344") (pin "2") (pinfunction "2_2") (pintype "passive"))
      (node (ref "R296") (pin "1") (pinfunction "1_1") (pintype "passive"))
      (node (ref "R379") (pin "1") (pinfunction "1_1") (pintype "passive"))
      (node (ref "R386") (pin "2") (pinfunction "2_2") (pintype "passive"))
    )
    (net (code "48") (name "Net-(C359-Pad1)") (class "Default")
      (node (ref "C359") (pin "1") (pinfunction "1_1") (pintype "passive"))
      (node (ref "R534") (pin "2") (pinfunction "2_2") (pintype "passive"))
    )
    (net (code "49") (name "Net-(IC15-NR)") (class "Default")
      (node (ref "C118") (pin "2") (pinfunction "2_2") (pintype "passive"))
      (node (ref "IC15") (pin "5") (pinfunction "NR_5") (pintype "passive"))
    )
    (net (code "50") (name "Net-(IC31-CKIN2+)") (class "Default")
      (node (ref "C181") (pin "1") (pinfunction "1_1") (pintype "passive"))
      (node (ref "IC31") (pin "12") (pinfunction "CKIN2+_12") (pintype "input"))
    )
    (net (code "51") (name "Net-(IC31-CKIN2-)") (class "Default")
      (node (ref "C182") (pin "1") (pinfunction "1_1") (pintype "passive"))
      (node (ref "IC31") (pin "13") (pinfunction "CKIN2-_13") (pintype "input"))
    )
    (net (code "52") (name "Net-(IC31-CKOUT2+)") (class "Default")
      (node (ref "C183") (pin "2") (pinfunction "2_2") (pintype "passive"))
      (node (ref "IC31") (pin "35") (pinfunction "CKOUT2+_35") (pintype "output"))
      (node (ref "TP29") (pin "1") (pinfunction "1_1") (pintype "bidirectional"))
    )
    (net (code "53") (name "Net-(IC31-CKOUT2-)") (class "Default")
      (node (ref "C184") (pin "2") (pinfunction "2_2") (pintype "passive"))
      (node (ref "IC31") (pin "34") (pinfunction "CKOUT2-_34") (pintype "output"))
      (node (ref "TP30") (pin "1") (pinfunction "1_1") (pintype "bidirectional"))
    )
    (net (code "54") (name "Net-(IC31-CS_CA)") (class "Default")
      (node (ref "IC31") (pin "21") (pinfunction "CS_CA_21") (pintype "bidirectional"))
      (node (ref "R55") (pin "2") (pinfunction "2_2") (pintype "passive"))
    )
    (net (code "55") (name "Net-(IC44-Q0)") (class "Default")
      (node (ref "IC44") (pin "30") (pinfunction "Q0_30") (pintype "output"))
      (node (ref "R366") (pin "1") (pinfunction "1_1") (pintype "passive"))
      (node (ref "R531") (pin "1") (pinfunction "1_1") (pintype "passive"))
    )
    (net (code "56") (name "Net-(IC44-Q1)") (class "Default")
      (node (ref "IC44") (pin "28") (pinfunction "Q1_28") (pintype "output"))
      (node (ref "R369") (pin "1") (pinfunction "1_1") (pintype "passive"))
      (node (ref "R533") (pin "1") (pinfunction "1_1") (pintype "passive"))
    )
    (net (code "57") (name "Net-(IC44-Q3)") (class "Default")
      (node (ref "IC44") (pin "22") (pinfunction "Q3_22") (pintype "output"))
      (node (ref "R133") (pin "1") (pinfunction "1_1") (pintype "passive"))
      (node (ref "R134") (pin "1") (pinfunction "1_1") (pintype "passive"))
    )
    (net (code "58") (name "Net-(IC44-Q7)") (class "Default")
      (node (ref "C137") (pin "1") (pinfunction "1_1") (pintype "passive"))
      (node (ref "IC44") (pin "12") (pinfunction "Q7_12") (pintype "output"))
      (node (ref "R373") (pin "1") (pinfunction "1_1") (pintype "passive"))
    )
    (net (code "59") (name "Net-(IC44-VREF0)") (class "Default")
      (node (ref "IC44") (pin "3") (pinfunction "VREF0_3") (pintype "input"))
      (node (ref "R372") (pin "2") (pinfunction "2_2") (pintype "passive"))
    )
    (net (code "60") (name "Net-(IC44-VREF1)") (class "Default")
      (node (ref "IC44") (pin "8") (pinfunction "VREF1_8") (pintype "input"))
      (node (ref "R380") (pin "2") (pinfunction "2_2") (pintype "passive"))
    )
    (net (code "61") (name "Net-(IC44-VT0)") (class "Default")
      (node (ref "C372") (pin "2") (pinfunction "2_2") (pintype "passive"))
      (node (ref "IC44") (pin "4") (pinfunction "VT0_4") (pintype "passive"))
      (node (ref "R372") (pin "1") (pinfunction "1_1") (pintype "passive"))
    )
    (net (code "62") (name "Net-(IC44-VT1)") (class "Default")
      (node (ref "C130") (pin "2") (pinfunction "2_2") (pintype "passive"))
      (node (ref "IC44") (pin "7") (pinfunction "VT1_7") (pintype "passive"))
      (node (ref "R380") (pin "1") (pinfunction "1_1") (pintype "passive"))
    )
    (net (code "63") (name "Net-(IC44-~{Q0})") (class "Default")
      (node (ref "IC44") (pin "29") (pinfunction "~{Q0}_29") (pintype "output"))
      (node (ref "R368") (pin "1") (pinfunction "1_1") (pintype "passive"))
      (node (ref "R532") (pin "1") (pinfunction "1_1") (pintype "passive"))
    )
    (net (code "64") (name "Net-(IC44-~{Q1})") (class "Default")
      (node (ref "IC44") (pin "27") (pinfunction "~{Q1}_27") (pintype "output"))
      (node (ref "R371") (pin "1") (pinfunction "1_1") (pintype "passive"))
      (node (ref "R534") (pin "1") (pinfunction "1_1") (pintype "passive"))
    )
    (net (code "65") (name "Net-(IC44-~{Q3})") (class "Default")
      (node (ref "IC44") (pin "21") (pinfunction "~{Q3}_21") (pintype "output"))
      (node (ref "R333") (pin "1") (pinfunction "1_1") (pintype "passive"))
      (node (ref "R334") (pin "1") (pinfunction "1_1") (pintype "passive"))
    )
    (net (code "66") (name "Net-(IC44-~{Q7})") (class "Default")
      (node (ref "C136") (pin "1") (pinfunction "1_1") (pintype "passive"))
      (node (ref "IC44") (pin "11") (pinfunction "~{Q7}_11") (pintype "output"))
      (node (ref "R374") (pin "1") (pinfunction "1_1") (pintype "passive"))
    )
    (net (code "67") (name "Net-(J33-Pad1)") (class "Default")
      (node (ref "J33") (pin "1") (pinfunction "1_1") (pintype "bidirectional"))
      (node (ref "R386") (pin "1") (pinfunction "1_1") (pintype "passive"))
    )
    (net (code "68") (name "Net-(OSC4-CLK+)") (class "Default")
      (node (ref "OSC4") (pin "4") (pinfunction "CLK+_4") (pintype "passive"))
      (node (ref "R376") (pin "2") (pinfunction "2_2") (pintype "passive"))
    )
    (net (code "69") (name "Net-(OSC4-CLK-)") (class "Default")
      (node (ref "C127") (pin "1") (pinfunction "1_1") (pintype "passive"))
      (node (ref "OSC4") (pin "5") (pinfunction "CLK-_5") (pintype "passive"))
      (node (ref "R360") (pin "2") (pinfunction "2_2") (pintype "passive"))
    )
    (net (code "70") (name "Net-(OSC4-NC)") (class "Default")
      (node (ref "OSC4") (pin "2") (pinfunction "NC_2") (pintype "passive"))
      (node (ref "R382") (pin "1") (pinfunction "1_1") (pintype "passive"))
    )
    (net (code "71") (name "Net-(OSC4-OE)") (class "Default")
      (node (ref "OSC4") (pin "1") (pinfunction "OE_1") (pintype "passive"))
      (node (ref "R384") (pin "1") (pinfunction "1_1") (pintype "passive"))
    )
    (net (code "72") (name "Net-(OSC4-VDD)") (class "Default")
      (node (ref "C123") (pin "2") (pinfunction "2_2") (pintype "passive"))
      (node (ref "C124") (pin "2") (pinfunction "2_2") (pintype "passive"))
      (node (ref "C351") (pin "2") (pinfunction "2_2") (pintype "passive"))
      (node (ref "L18") (pin "2") (pinfunction "2_2") (pintype "passive"))
      (node (ref "OSC4") (pin "6") (pinfunction "VDD_6") (pintype "passive"))
    )
    (net (code "73") (name "Net-(OSC5-CLK+)") (class "Default")
      (node (ref "OSC5") (pin "4") (pinfunction "CLK+_4") (pintype "passive"))
      (node (ref "R377") (pin "2") (pinfunction "2_2") (pintype "passive"))
    )
    (net (code "74") (name "Net-(OSC5-CLK-)") (class "Default")
      (node (ref "C138") (pin "1") (pinfunction "1_1") (pintype "passive"))
      (node (ref "OSC5") (pin "5") (pinfunction "CLK-_5") (pintype "passive"))
      (node (ref "R363") (pin "2") (pinfunction "2_2") (pintype "passive"))
    )
    (net (code "75") (name "Net-(OSC5-NC)") (class "Default")
      (node (ref "OSC5") (pin "2") (pinfunction "NC_2") (pintype "passive"))
      (node (ref "R383") (pin "1") (pinfunction "1_1") (pintype "passive"))
    )
    (net (code "76") (name "Net-(OSC5-OE)") (class "Default")
      (node (ref "OSC5") (pin "1") (pinfunction "OE_1") (pintype "passive"))
      (node (ref "R385") (pin "1") (pinfunction "1_1") (pintype "passive"))
    )
    (net (code "77") (name "Net-(OSC5-VDD)") (class "Default")
      (node (ref "C139") (pin "2") (pinfunction "2_2") (pintype "passive"))
      (node (ref "C356") (pin "2") (pinfunction "2_2") (pintype "passive"))
      (node (ref "C658") (pin "2") (pinfunction "2_2") (pintype "passive"))
      (node (ref "L38") (pin "2") (pinfunction "2_2") (pintype "passive"))
      (node (ref "OSC5") (pin "6") (pinfunction "VDD_6") (pintype "passive"))
    )
    (net (code "78") (name "P3V3_CLK") (class "Default")
      (node (ref "C330") (pin "2") (pinfunction "2_2") (pintype "passive"))
      (node (ref "C655") (pin "2") (pinfunction "2_2") (pintype "passive"))
      (node (ref "IC15") (pin "4") (pinfunction "OUT_4") (pintype "power_in"))
      (node (ref "L16") (pin "1") (pinfunction "1_1") (pintype "passive"))
      (node (ref "L18") (pin "1") (pinfunction "1_1") (pintype "passive"))
      (node (ref "L33") (pin "1") (pinfunction "1_1") (pintype "passive"))
      (node (ref "L38") (pin "1") (pinfunction "1_1") (pintype "passive"))
      (node (ref "R381") (pin "1") (pinfunction "1_1") (pintype "passive"))
      (node (ref "TP76") (pin "1") (pinfunction "1_1") (pintype "bidirectional"))
    )
    (net (code "79") (name "P4V0") (class "Default")
      (node (ref "L17") (pin "1") (pinfunction "1_1") (pintype "passive"))
    )
    (net (code "80") (name "unconnected-(C121-Pad2)") (class "Default")
      (node (ref "C121") (pin "2") (pinfunction "2_2") (pintype "passive"))
    )
    (net (code "81") (name "unconnected-(C122-Pad2)") (class "Default")
      (node (ref "C122") (pin "2") (pinfunction "2_2") (pintype "passive"))
    )
    (net (code "82") (name "unconnected-(C125-Pad2)") (class "Default")
      (node (ref "C125") (pin "2") (pinfunction "2_2") (pintype "passive"))
    )
    (net (code "83") (name "unconnected-(C128-Pad2)") (class "Default")
      (node (ref "C128") (pin "2") (pinfunction "2_2") (pintype "passive"))
    )
    (net (code "84") (name "unconnected-(C129-Pad2)") (class "Default")
      (node (ref "C129") (pin "2") (pinfunction "2_2") (pintype "passive"))
    )
    (net (code "85") (name "unconnected-(C359-Pad2)") (class "Default")
      (node (ref "C359") (pin "2") (pinfunction "2_2") (pintype "passive"))
    )
    (net (code "86") (name "unconnected-(IC31-C2B-Pad4)") (class "Default")
      (node (ref "IC31") (pin "4") (pinfunction "C2B_4") (pintype "output+no_connect"))
    )
    (net (code "87") (name "unconnected-(IC31-CKOUT1+-Pad28)") (class "Default")
      (node (ref "IC31") (pin "28") (pinfunction "CKOUT1+_28") (pintype "output+no_connect"))
    )
    (net (code "88") (name "unconnected-(IC31-CKOUT1--Pad29)") (class "Default")
      (node (ref "IC31") (pin "29") (pinfunction "CKOUT1-_29") (pintype "output+no_connect"))
    )
    (net (code "89") (name "unconnected-(IC31-LOL-Pad18)") (class "Default")
      (node (ref "IC31") (pin "18") (pinfunction "LOL_18") (pintype "output+no_connect"))
    )
    (net (code "90") (name "unconnected-(IC31-NC-Pad2)") (class "Default")
      (node (ref "IC31") (pin "2") (pinfunction "NC_2") (pintype "passive+no_connect"))
    )
    (net (code "91") (name "unconnected-(IC31-NC-Pad9)") (class "Default")
      (node (ref "IC31") (pin "9") (pinfunction "NC_9") (pintype "passive+no_connect"))
    )
    (net (code "92") (name "unconnected-(IC31-NC-Pad14)") (class "Default")
      (node (ref "IC31") (pin "14") (pinfunction "NC_14") (pintype "passive+no_connect"))
    )
    (net (code "93") (name "unconnected-(IC31-NC-Pad30)") (class "Default")
      (node (ref "IC31") (pin "30") (pinfunction "NC_30") (pintype "passive+no_connect"))
    )
    (net (code "94") (name "unconnected-(IC31-NC-Pad33)") (class "Default")
      (node (ref "IC31") (pin "33") (pinfunction "NC_33") (pintype "passive+no_connect"))
    )
    (net (code "95") (name "unconnected-(IC31-RATE0-Pad11)") (class "Default")
      (node (ref "IC31") (pin "11") (pinfunction "RATE0_11") (pintype "input+no_connect"))
    )
    (net (code "96") (name "unconnected-(IC31-RATE1-Pad15)") (class "Default")
      (node (ref "IC31") (pin "15") (pinfunction "RATE1_15") (pintype "input+no_connect"))
    )
    (net (code "97") (name "unconnected-(IC31-SDI-Pad27)") (class "Default")
      (node (ref "IC31") (pin "27") (pinfunction "SDI_27") (pintype "input+no_connect"))
    )
    (net (code "98") (name "unconnected-(IC44-NC-Pad9)") (class "Default")
      (node (ref "IC44") (pin "9") (pinfunction "NC_9") (pintype "passive+no_connect"))
    )
    (net (code "99") (name "unconnected-(IC44-Q2-Pad24)") (class "Default")
      (node (ref "IC44") (pin "24") (pinfunction "Q2_24") (pintype "output"))
    )
    (net (code "100") (name "unconnected-(IC44-Q4-Pad20)") (class "Default")
      (node (ref "IC44") (pin "20") (pinfunction "Q4_20") (pintype "output"))
    )
    (net (code "101") (name "unconnected-(IC44-Q5-Pad18)") (class "Default")
      (node (ref "IC44") (pin "18") (pinfunction "Q5_18") (pintype "output"))
    )
    (net (code "102") (name "unconnected-(IC44-Q6-Pad14)") (class "Default")
      (node (ref "IC44") (pin "14") (pinfunction "Q6_14") (pintype "output+no_connect"))
    )
    (net (code "103") (name "unconnected-(IC44-~{Q2}-Pad23)") (class "Default")
      (node (ref "IC44") (pin "23") (pinfunction "~{Q2}_23") (pintype "output"))
    )
    (net (code "104") (name "unconnected-(IC44-~{Q4}-Pad19)") (class "Default")
      (node (ref "IC44") (pin "19") (pinfunction "~{Q4}_19") (pintype "output"))
    )
    (net (code "105") (name "unconnected-(IC44-~{Q5}-Pad17)") (class "Default")
      (node (ref "IC44") (pin "17") (pinfunction "~{Q5}_17") (pintype "output"))
    )
    (net (code "106") (name "unconnected-(IC44-~{Q6}-Pad13)") (class "Default")
      (node (ref "IC44") (pin "13") (pinfunction "~{Q6}_13") (pintype "output+no_connect"))
    )
    (net (code "107") (name "unconnected-(R296-Pad2)") (class "Default")
      (node (ref "R296") (pin "2") (pinfunction "2_2") (pintype "passive"))
    )
    (net (code "108") (name "unconnected-(R297-Pad2)") (class "Default")
      (node (ref "R297") (pin "2") (pinfunction "2_2") (pintype "passive"))
    )
  )
)
